# SCH_L298N__2024-03-01.net
KiCad netlist of a schematic drawn in EasyEDA
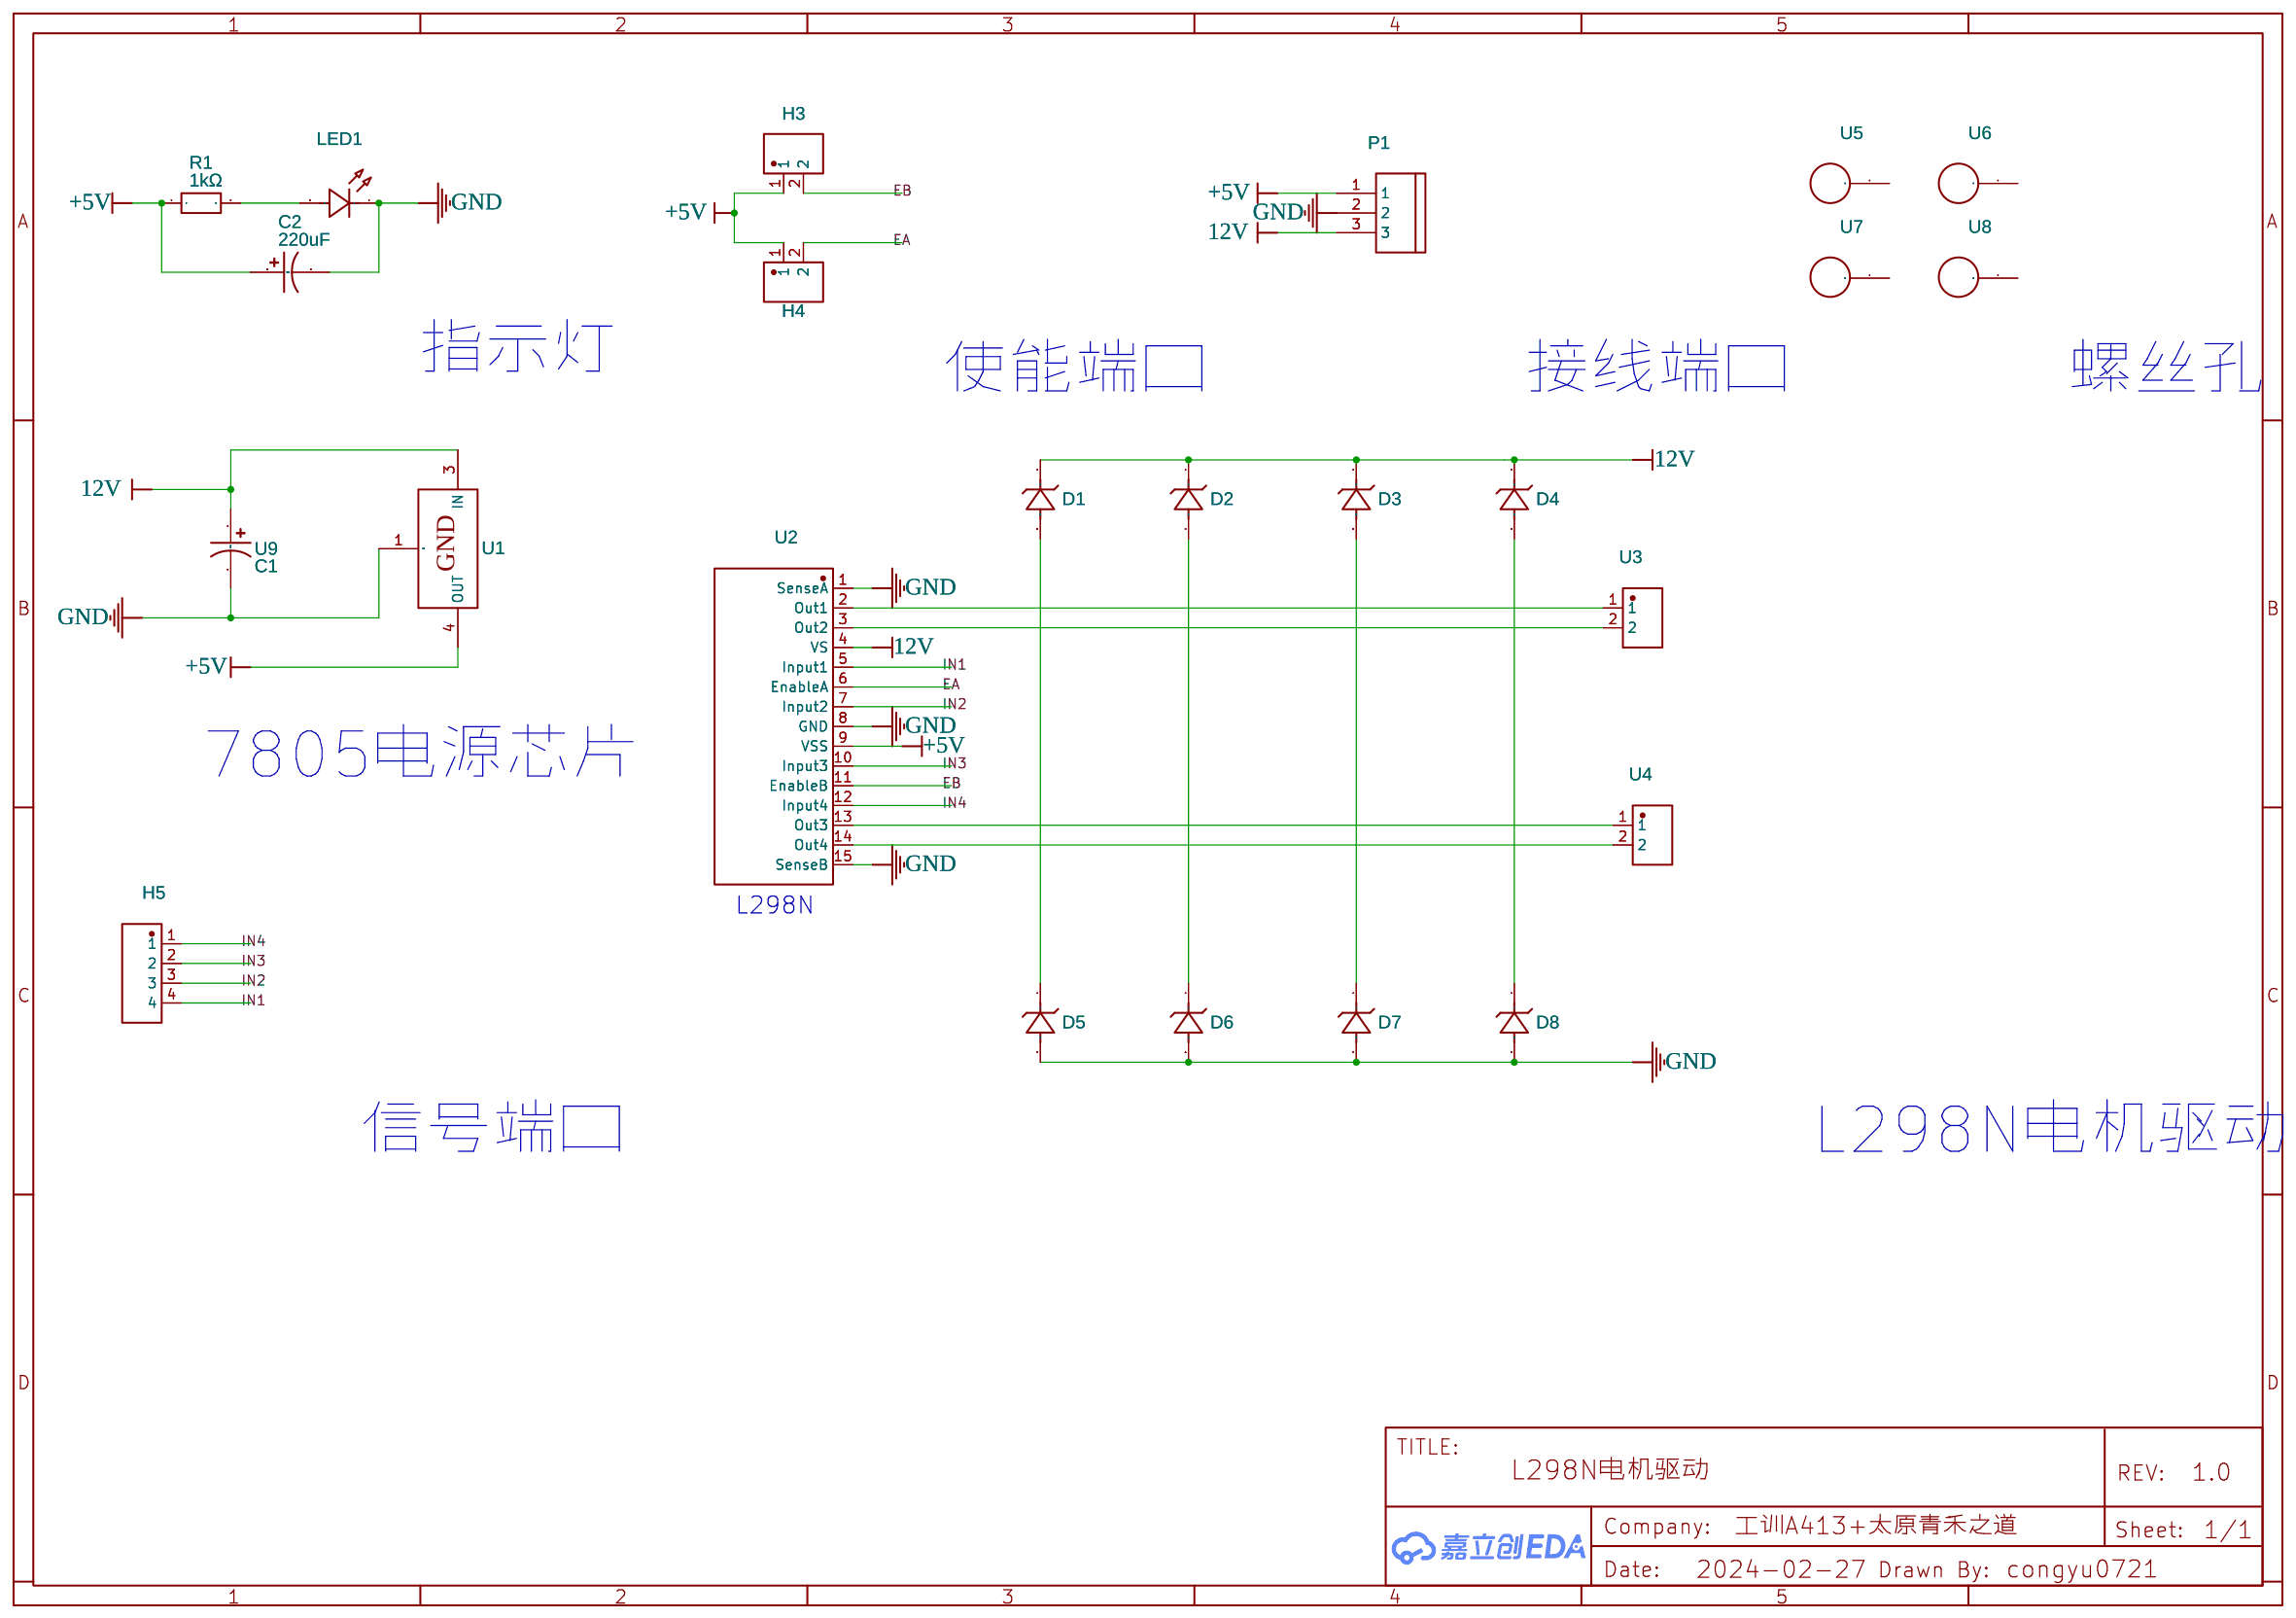
[diagram p0: schematic sheet]

(export (version "E")
  (design (tool "Eeschema 10.0.6"))
  (components
    (comp (ref "C2")
      (value "220uF")
      (fields
        (field (name "Manufacturer Part") "HY1V221MC080105MEO")
        (field (name "Manufacturer") "HYNCDZ(宏远纳川)")
      )
      (libsource (lib "") (part "HY1V221MC080105MEO_1"))
    )
    (comp (ref "D1")
      (value "SMF15A_C19077509")
      (fields (field (name "Manufacturer Part") "SMF15A") (field (name "Manufacturer") "宏迦橙"))
      (libsource (lib "") (part "SMF15A_C19077509"))
    )
    (comp (ref "D2")
      (value "SMF15A_C19077509")
      (fields (field (name "Manufacturer Part") "SMF15A") (field (name "Manufacturer") "宏迦橙"))
      (libsource (lib "") (part "SMF15A_C19077509"))
    )
    (comp (ref "D3")
      (value "SMF15A_C19077509")
      (fields (field (name "Manufacturer Part") "SMF15A") (field (name "Manufacturer") "宏迦橙"))
      (libsource (lib "") (part "SMF15A_C19077509"))
    )
    (comp (ref "D4")
      (value "SMF15A_C19077509")
      (fields (field (name "Manufacturer Part") "SMF15A") (field (name "Manufacturer") "宏迦橙"))
      (libsource (lib "") (part "SMF15A_C19077509"))
    )
    (comp (ref "D5")
      (value "SMF15A_C19077509")
      (fields (field (name "Manufacturer Part") "SMF15A") (field (name "Manufacturer") "宏迦橙"))
      (libsource (lib "") (part "SMF15A_C19077509"))
    )
    (comp (ref "D6")
      (value "SMF15A_C19077509")
      (fields (field (name "Manufacturer Part") "SMF15A") (field (name "Manufacturer") "宏迦橙"))
      (libsource (lib "") (part "SMF15A_C19077509"))
    )
    (comp (ref "D7")
      (value "SMF15A_C19077509")
      (fields (field (name "Manufacturer Part") "SMF15A") (field (name "Manufacturer") "宏迦橙"))
      (libsource (lib "") (part "SMF15A_C19077509"))
    )
    (comp (ref "D8")
      (value "SMF15A_C19077509")
      (fields (field (name "Manufacturer Part") "SMF15A") (field (name "Manufacturer") "宏迦橙"))
      (libsource (lib "") (part "SMF15A_C19077509"))
    )
    (comp (ref "H3")
      (value "DB302-5.0-2P-GN-S")
      (fields (field (name "Manufacturer") "DORABO(地博电气)"))
      (libsource (lib "") (part "DB302-5.0-2P-GN-S_2"))
    )
    (comp (ref "H4")
      (value "DB302-5.0-2P-GN-S")
      (fields (field (name "Manufacturer") "DORABO(地博电气)"))
      (libsource (lib "") (part "DB302-5.0-2P-GN-S_1"))
    )
    (comp (ref "H5")
      (value "826629-4")
      (fields (field (name "Manufacturer") "TE Connectivity(泰科电子)"))
      (libsource (lib "") (part "826629-4"))
    )
    (comp (ref "LED1")
      (value "RF-BGB170TS-CB-E0")
      (fields (field (name "Manufacturer") "Refond(瑞丰)"))
      (libsource (lib "") (part "RF-BGB170TS-CB-E0"))
    )
    (comp (ref "P1")
      (value "WJ500V-5.08-3P-14-00A")
      (fields
        (field (name "Manufacturer Part") "WJ500V-5.08-3P")
        (field (name "Manufacturer") "KANGNEX(康奈克斯电气)")
      )
      (libsource (lib "") (part "WJ500V-5.08-3P-14-00A"))
    )
    (comp (ref "R1")
      (value "1kΩ")
      (fields (field (name "Manufacturer Part") "PTFR0805Q1K00P9") (field (name "Manufacturer") "RESI(开步睿思）"))
      (libsource (lib "") (part "PTFR0805Q1K00P9"))
    )
    (comp (ref "U1")
      (value "LD1086DT33TR")
      (fields (field (name "Manufacturer") "ST(意法半导体)"))
      (libsource (lib "") (part "LD1086DT33TR"))
    )
    (comp (ref "U2")
      (value "L298N-HXY")
      (fields (field (name "Manufacturer") "HXY MOSFET(华轩阳电子)"))
      (libsource (lib "") (part "L298N-HXY"))
    )
    (comp (ref "U3")
      (value "DB302-5.0-2P-GN-S")
      (fields (field (name "Manufacturer") "DORABO(地博电气)"))
      (libsource (lib "") (part "DB302-5.0-2P-GN-S"))
    )
    (comp (ref "U4")
      (value "DB302-5.0-2P-GN-S")
      (fields (field (name "Manufacturer") "DORABO(地博电气)"))
      (libsource (lib "") (part "DB302-5.0-2P-GN-S"))
    )
    (comp (ref "U5")
      (value "铜柱M3*5+6")
      (fields (field (name "Manufacturer") "国产"))
      (libsource (lib "") (part "铜柱M3*5+6"))
    )
    (comp (ref "U6")
      (value "铜柱M3*5+6")
      (fields (field (name "Manufacturer") "国产"))
      (libsource (lib "") (part "铜柱M3*5+6"))
    )
    (comp (ref "U7")
      (value "铜柱M3*5+6")
      (fields (field (name "Manufacturer") "国产"))
      (libsource (lib "") (part "铜柱M3*5+6_1"))
    )
    (comp (ref "U8")
      (value "铜柱M3*5+6")
      (fields (field (name "Manufacturer") "国产"))
      (libsource (lib "") (part "铜柱M3*5+6_1"))
    )
    (comp (ref "U9")
      (value "C1")
      (fields
        (field (name "Manufacturer Part") "HY1V221MC080105MEO")
        (field (name "Manufacturer") "HYNCDZ(宏远纳川)")
      )
      (libsource (lib "") (part "HY1V221MC080105MEO"))
    )
  )
  (nets
    (net (code "1") (name "+5V") (class "Default")
      (node (ref "C2") (pin "1") (pinfunction "1_1") (pintype "unspecified"))
      (node (ref "H3") (pin "1") (pinfunction "1_1") (pintype "unspecified"))
      (node (ref "H4") (pin "1") (pinfunction "1_1") (pintype "unspecified"))
      (node (ref "P1") (pin "1") (pinfunction "1_1") (pintype "unspecified"))
      (node (ref "R1") (pin "1") (pinfunction "1_1") (pintype "unspecified"))
      (node (ref "U1") (pin "4") (pinfunction "OUT_4") (pintype "passive"))
      (node (ref "U2") (pin "9") (pinfunction "VSS_9") (pintype "unspecified"))
    )
    (net (code "2") (name "/EA") (class "Default")
      (node (ref "H4") (pin "2") (pinfunction "2_2") (pintype "unspecified"))
      (node (ref "U2") (pin "6") (pinfunction "EnableA_6") (pintype "unspecified"))
    )
    (net (code "3") (name "/EB") (class "Default")
      (node (ref "H3") (pin "2") (pinfunction "2_2") (pintype "unspecified"))
      (node (ref "U2") (pin "11") (pinfunction "EnableB_11") (pintype "unspecified"))
    )
    (net (code "4") (name "/IN1") (class "Default")
      (node (ref "H5") (pin "4") (pinfunction "4_4") (pintype "unspecified"))
      (node (ref "U2") (pin "5") (pinfunction "Input1_5") (pintype "unspecified"))
    )
    (net (code "5") (name "/IN2") (class "Default")
      (node (ref "H5") (pin "3") (pinfunction "3_3") (pintype "unspecified"))
      (node (ref "U2") (pin "7") (pinfunction "Input2_7") (pintype "unspecified"))
    )
    (net (code "6") (name "/IN3") (class "Default")
      (node (ref "H5") (pin "2") (pinfunction "2_2") (pintype "unspecified"))
      (node (ref "U2") (pin "10") (pinfunction "Input3_10") (pintype "unspecified"))
    )
    (net (code "7") (name "/IN4") (class "Default")
      (node (ref "H5") (pin "1") (pinfunction "1_1") (pintype "unspecified"))
      (node (ref "U2") (pin "12") (pinfunction "Input4_12") (pintype "unspecified"))
    )
    (net (code "8") (name "12V") (class "Default")
      (node (ref "D1") (pin "1") (pinfunction "K_1") (pintype "unspecified"))
      (node (ref "D2") (pin "1") (pinfunction "K_1") (pintype "unspecified"))
      (node (ref "D3") (pin "1") (pinfunction "K_1") (pintype "unspecified"))
      (node (ref "D4") (pin "1") (pinfunction "K_1") (pintype "unspecified"))
      (node (ref "P1") (pin "3") (pinfunction "3_3") (pintype "unspecified"))
      (node (ref "U1") (pin "3") (pinfunction "IN_3") (pintype "passive"))
      (node (ref "U2") (pin "4") (pinfunction "VS_4") (pintype "unspecified"))
      (node (ref "U9") (pin "1") (pinfunction "1_1") (pintype "unspecified"))
    )
    (net (code "9") (name "GND") (class "Default")
      (node (ref "C2") (pin "2") (pinfunction "2_2") (pintype "unspecified"))
      (node (ref "D5") (pin "2") (pinfunction "A_2") (pintype "unspecified"))
      (node (ref "D6") (pin "2") (pinfunction "A_2") (pintype "unspecified"))
      (node (ref "D7") (pin "2") (pinfunction "A_2") (pintype "unspecified"))
      (node (ref "D8") (pin "2") (pinfunction "A_2") (pintype "unspecified"))
      (node (ref "LED1") (pin "1") (pinfunction "K_1") (pintype "unspecified"))
      (node (ref "P1") (pin "2") (pinfunction "2_2") (pintype "unspecified"))
      (node (ref "U1") (pin "1") (pinfunction "GND_1") (pintype "passive"))
      (node (ref "U2") (pin "1") (pinfunction "SenseA_1") (pintype "unspecified"))
      (node (ref "U2") (pin "15") (pinfunction "SenseB_15") (pintype "unspecified"))
      (node (ref "U2") (pin "8") (pinfunction "GND_8") (pintype "unspecified"))
      (node (ref "U9") (pin "2") (pinfunction "2_2") (pintype "unspecified"))
    )
    (net (code "10") (name "Net-(D1-A)") (class "Default")
      (node (ref "D1") (pin "2") (pinfunction "A_2") (pintype "unspecified"))
      (node (ref "D5") (pin "1") (pinfunction "K_1") (pintype "unspecified"))
    )
    (net (code "11") (name "Net-(D2-A)") (class "Default")
      (node (ref "D2") (pin "2") (pinfunction "A_2") (pintype "unspecified"))
      (node (ref "D6") (pin "1") (pinfunction "K_1") (pintype "unspecified"))
    )
    (net (code "12") (name "Net-(D3-A)") (class "Default")
      (node (ref "D3") (pin "2") (pinfunction "A_2") (pintype "unspecified"))
      (node (ref "D7") (pin "1") (pinfunction "K_1") (pintype "unspecified"))
    )
    (net (code "13") (name "Net-(D4-A)") (class "Default")
      (node (ref "D4") (pin "2") (pinfunction "A_2") (pintype "unspecified"))
      (node (ref "D8") (pin "1") (pinfunction "K_1") (pintype "unspecified"))
    )
    (net (code "14") (name "Net-(LED1-A)") (class "Default")
      (node (ref "LED1") (pin "2") (pinfunction "A_2") (pintype "unspecified"))
      (node (ref "R1") (pin "2") (pinfunction "2_2") (pintype "unspecified"))
    )
    (net (code "15") (name "Net-(U2-Out1)") (class "Default")
      (node (ref "U2") (pin "2") (pinfunction "Out1_2") (pintype "unspecified"))
      (node (ref "U3") (pin "1") (pinfunction "1_1") (pintype "unspecified"))
    )
    (net (code "16") (name "Net-(U2-Out2)") (class "Default")
      (node (ref "U2") (pin "3") (pinfunction "Out2_3") (pintype "unspecified"))
      (node (ref "U3") (pin "2") (pinfunction "2_2") (pintype "unspecified"))
    )
    (net (code "17") (name "Net-(U2-Out3)") (class "Default")
      (node (ref "U2") (pin "13") (pinfunction "Out3_13") (pintype "unspecified"))
      (node (ref "U4") (pin "1") (pinfunction "1_1") (pintype "unspecified"))
    )
    (net (code "18") (name "Net-(U2-Out4)") (class "Default")
      (node (ref "U2") (pin "14") (pinfunction "Out4_14") (pintype "unspecified"))
      (node (ref "U4") (pin "2") (pinfunction "2_2") (pintype "unspecified"))
    )
    (net (code "19") (name "unconnected-(U5-Pad1)") (class "Default")
      (node (ref "U5") (pin "1") (pinfunction "1_1") (pintype "unspecified"))
    )
    (net (code "20") (name "unconnected-(U6-Pad1)") (class "Default")
      (node (ref "U6") (pin "1") (pinfunction "1_1") (pintype "unspecified"))
    )
    (net (code "21") (name "unconnected-(U7-Pad1)") (class "Default")
      (node (ref "U7") (pin "1") (pinfunction "1_1") (pintype "unspecified"))
    )
    (net (code "22") (name "unconnected-(U8-Pad1)") (class "Default")
      (node (ref "U8") (pin "1") (pinfunction "1_1") (pintype "unspecified"))
    )
  )
)
